# micro.net
KiCad netlist of a schematic drawn in EAGLE
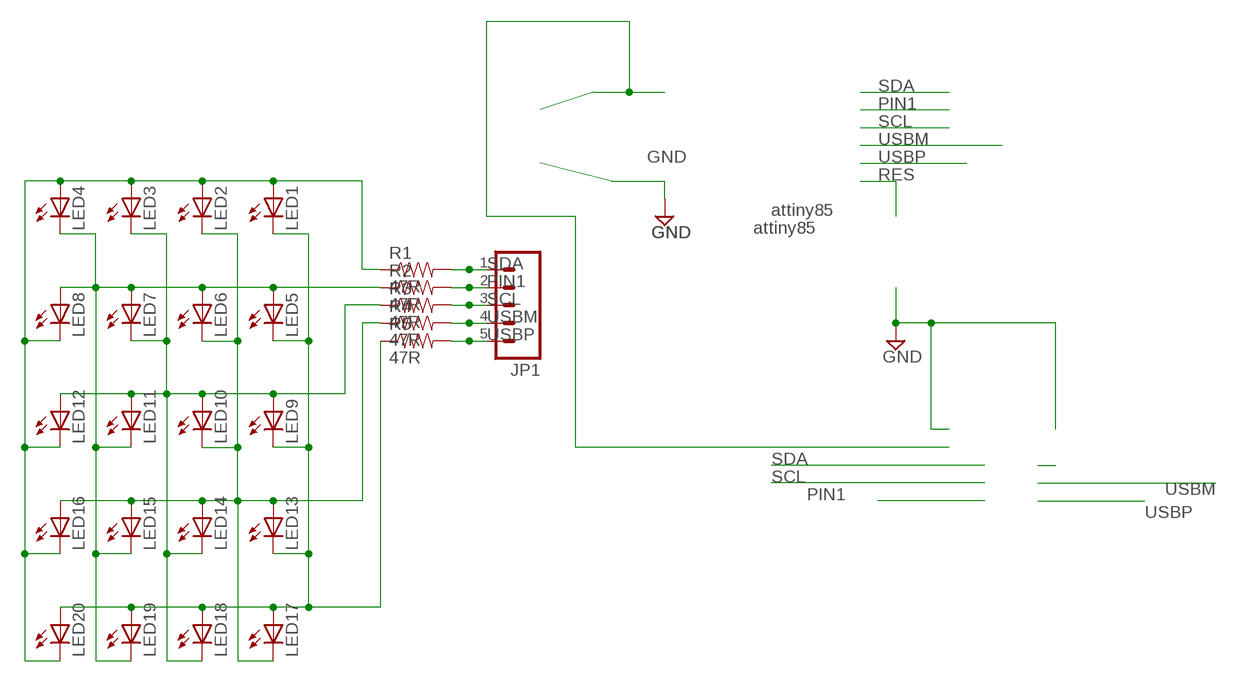
[diagram p0: schematic, sheet 1]

(export (version "E")
  (design (tool "Eeschema 10.0.6"))
  (components
    (comp (ref "JP1")
      (value "M05PTH")
      (footprint "eagle-import:1X05")
      (libsource (lib "eagle-import") (part "M05PTH"))
    )
    (comp (ref "LED1")
      (value "LEDCHIPLED_0603")
      (footprint "eagle-import:CHIPLED_0603")
      (libsource (lib "eagle-import") (part "LEDCHIPLED_0603"))
    )
    (comp (ref "LED2")
      (value "LEDCHIPLED_0603")
      (footprint "eagle-import:CHIPLED_0603")
      (libsource (lib "eagle-import") (part "LEDCHIPLED_0603"))
    )
    (comp (ref "LED3")
      (value "LEDCHIPLED_0603")
      (footprint "eagle-import:CHIPLED_0603")
      (libsource (lib "eagle-import") (part "LEDCHIPLED_0603"))
    )
    (comp (ref "LED4")
      (value "LEDCHIPLED_0603")
      (footprint "eagle-import:CHIPLED_0603")
      (libsource (lib "eagle-import") (part "LEDCHIPLED_0603"))
    )
    (comp (ref "LED5")
      (value "LEDCHIPLED_0603")
      (footprint "eagle-import:CHIPLED_0603")
      (libsource (lib "eagle-import") (part "LEDCHIPLED_0603"))
    )
    (comp (ref "LED6")
      (value "LEDCHIPLED_0603")
      (footprint "eagle-import:CHIPLED_0603")
      (libsource (lib "eagle-import") (part "LEDCHIPLED_0603"))
    )
    (comp (ref "LED7")
      (value "LEDCHIPLED_0603")
      (footprint "eagle-import:CHIPLED_0603")
      (libsource (lib "eagle-import") (part "LEDCHIPLED_0603"))
    )
    (comp (ref "LED8")
      (value "LEDCHIPLED_0603")
      (footprint "eagle-import:CHIPLED_0603")
      (libsource (lib "eagle-import") (part "LEDCHIPLED_0603"))
    )
    (comp (ref "LED9")
      (value "LEDCHIPLED_0603")
      (footprint "eagle-import:CHIPLED_0603")
      (libsource (lib "eagle-import") (part "LEDCHIPLED_0603"))
    )
    (comp (ref "LED10")
      (value "LEDCHIPLED_0603")
      (footprint "eagle-import:CHIPLED_0603")
      (libsource (lib "eagle-import") (part "LEDCHIPLED_0603"))
    )
    (comp (ref "LED11")
      (value "LEDCHIPLED_0603")
      (footprint "eagle-import:CHIPLED_0603")
      (libsource (lib "eagle-import") (part "LEDCHIPLED_0603"))
    )
    (comp (ref "LED12")
      (value "LEDCHIPLED_0603")
      (footprint "eagle-import:CHIPLED_0603")
      (libsource (lib "eagle-import") (part "LEDCHIPLED_0603"))
    )
    (comp (ref "LED13")
      (value "LEDCHIPLED_0603")
      (footprint "eagle-import:CHIPLED_0603")
      (libsource (lib "eagle-import") (part "LEDCHIPLED_0603"))
    )
    (comp (ref "LED14")
      (value "LEDCHIPLED_0603")
      (footprint "eagle-import:CHIPLED_0603")
      (libsource (lib "eagle-import") (part "LEDCHIPLED_0603"))
    )
    (comp (ref "LED15")
      (value "LEDCHIPLED_0603")
      (footprint "eagle-import:CHIPLED_0603")
      (libsource (lib "eagle-import") (part "LEDCHIPLED_0603"))
    )
    (comp (ref "LED16")
      (value "LEDCHIPLED_0603")
      (footprint "eagle-import:CHIPLED_0603")
      (libsource (lib "eagle-import") (part "LEDCHIPLED_0603"))
    )
    (comp (ref "LED17")
      (value "LEDCHIPLED_0603")
      (footprint "eagle-import:CHIPLED_0603")
      (libsource (lib "eagle-import") (part "LEDCHIPLED_0603"))
    )
    (comp (ref "LED18")
      (value "LEDCHIPLED_0603")
      (footprint "eagle-import:CHIPLED_0603")
      (libsource (lib "eagle-import") (part "LEDCHIPLED_0603"))
    )
    (comp (ref "LED19")
      (value "LEDCHIPLED_0603")
      (footprint "eagle-import:CHIPLED_0603")
      (libsource (lib "eagle-import") (part "LEDCHIPLED_0603"))
    )
    (comp (ref "LED20")
      (value "LEDCHIPLED_0603")
      (footprint "eagle-import:CHIPLED_0603")
      (libsource (lib "eagle-import") (part "LEDCHIPLED_0603"))
    )
    (comp (ref "R1")
      (value "47R")
      (footprint "eagle-import:0603-RES")
      (libsource (lib "eagle-import") (part "RESISTOR0603-RES"))
    )
    (comp (ref "R2")
      (value "47R")
      (footprint "eagle-import:0603-RES")
      (libsource (lib "eagle-import") (part "RESISTOR0603-RES"))
    )
    (comp (ref "R3")
      (value "47R")
      (footprint "eagle-import:0603-RES")
      (libsource (lib "eagle-import") (part "RESISTOR0603-RES"))
    )
    (comp (ref "R4")
      (value "47R")
      (footprint "eagle-import:0603-RES")
      (libsource (lib "eagle-import") (part "RESISTOR0603-RES"))
    )
    (comp (ref "R5")
      (value "47R")
      (footprint "eagle-import:0603-RES")
      (libsource (lib "eagle-import") (part "RESISTOR0603-RES"))
    )
  )
  (nets
    (net (code "1") (name "/PIN1") (class "Default")
      (node (ref "JP1") (pin "2") (pinfunction "2_2") (pintype "passive"))
      (node (ref "R2") (pin "2") (pinfunction "2_2") (pintype "passive"))
    )
    (net (code "3") (name "/SCL") (class "Default")
      (node (ref "JP1") (pin "3") (pinfunction "3_3") (pintype "passive"))
      (node (ref "R3") (pin "2") (pinfunction "2_2") (pintype "passive"))
    )
    (net (code "4") (name "/SDA") (class "Default")
      (node (ref "JP1") (pin "1") (pinfunction "1_1") (pintype "passive"))
      (node (ref "R1") (pin "2") (pinfunction "2_2") (pintype "passive"))
    )
    (net (code "5") (name "/USBM") (class "Default")
      (node (ref "JP1") (pin "4") (pinfunction "4_4") (pintype "passive"))
      (node (ref "R4") (pin "2") (pinfunction "2_2") (pintype "passive"))
    )
    (net (code "6") (name "/USBP") (class "Default")
      (node (ref "JP1") (pin "5") (pinfunction "5_5") (pintype "passive"))
      (node (ref "R5") (pin "2") (pinfunction "2_2") (pintype "passive"))
    )
    (net (code "8") (name "Net-(LED1-PadA)") (class "Default")
      (node (ref "LED1") (pin "A") (pinfunction "A_A") (pintype "passive"))
      (node (ref "LED12") (pin "C") (pinfunction "C_C") (pintype "passive"))
      (node (ref "LED16") (pin "C") (pinfunction "C_C") (pintype "passive"))
      (node (ref "LED2") (pin "A") (pinfunction "A_A") (pintype "passive"))
      (node (ref "LED20") (pin "C") (pinfunction "C_C") (pintype "passive"))
      (node (ref "LED3") (pin "A") (pinfunction "A_A") (pintype "passive"))
      (node (ref "LED4") (pin "A") (pinfunction "A_A") (pintype "passive"))
      (node (ref "LED8") (pin "C") (pinfunction "C_C") (pintype "passive"))
      (node (ref "R1") (pin "1") (pinfunction "1_1") (pintype "passive"))
    )
    (net (code "9") (name "Net-(LED1-PadC)") (class "Default")
      (node (ref "LED1") (pin "C") (pinfunction "C_C") (pintype "passive"))
      (node (ref "LED13") (pin "C") (pinfunction "C_C") (pintype "passive"))
      (node (ref "LED17") (pin "A") (pinfunction "A_A") (pintype "passive"))
      (node (ref "LED18") (pin "A") (pinfunction "A_A") (pintype "passive"))
      (node (ref "LED19") (pin "A") (pinfunction "A_A") (pintype "passive"))
      (node (ref "LED20") (pin "A") (pinfunction "A_A") (pintype "passive"))
      (node (ref "LED5") (pin "C") (pinfunction "C_C") (pintype "passive"))
      (node (ref "LED9") (pin "C") (pinfunction "C_C") (pintype "passive"))
      (node (ref "R5") (pin "1") (pinfunction "1_1") (pintype "passive"))
    )
    (net (code "10") (name "Net-(LED10-PadA)") (class "Default")
      (node (ref "LED10") (pin "A") (pinfunction "A_A") (pintype "passive"))
      (node (ref "LED11") (pin "A") (pinfunction "A_A") (pintype "passive"))
      (node (ref "LED12") (pin "A") (pinfunction "A_A") (pintype "passive"))
      (node (ref "LED14") (pin "C") (pinfunction "C_C") (pintype "passive"))
      (node (ref "LED18") (pin "C") (pinfunction "C_C") (pintype "passive"))
      (node (ref "LED3") (pin "C") (pinfunction "C_C") (pintype "passive"))
      (node (ref "LED7") (pin "C") (pinfunction "C_C") (pintype "passive"))
      (node (ref "LED9") (pin "A") (pinfunction "A_A") (pintype "passive"))
      (node (ref "R3") (pin "1") (pinfunction "1_1") (pintype "passive"))
    )
    (net (code "11") (name "Net-(LED10-PadC)") (class "Default")
      (node (ref "LED10") (pin "C") (pinfunction "C_C") (pintype "passive"))
      (node (ref "LED13") (pin "A") (pinfunction "A_A") (pintype "passive"))
      (node (ref "LED14") (pin "A") (pinfunction "A_A") (pintype "passive"))
      (node (ref "LED15") (pin "A") (pinfunction "A_A") (pintype "passive"))
      (node (ref "LED16") (pin "A") (pinfunction "A_A") (pintype "passive"))
      (node (ref "LED17") (pin "C") (pinfunction "C_C") (pintype "passive"))
      (node (ref "LED2") (pin "C") (pinfunction "C_C") (pintype "passive"))
      (node (ref "LED6") (pin "C") (pinfunction "C_C") (pintype "passive"))
      (node (ref "R4") (pin "1") (pinfunction "1_1") (pintype "passive"))
    )
    (net (code "12") (name "Net-(LED11-PadC)") (class "Default")
      (node (ref "LED11") (pin "C") (pinfunction "C_C") (pintype "passive"))
      (node (ref "LED15") (pin "C") (pinfunction "C_C") (pintype "passive"))
      (node (ref "LED19") (pin "C") (pinfunction "C_C") (pintype "passive"))
      (node (ref "LED4") (pin "C") (pinfunction "C_C") (pintype "passive"))
      (node (ref "LED5") (pin "A") (pinfunction "A_A") (pintype "passive"))
      (node (ref "LED6") (pin "A") (pinfunction "A_A") (pintype "passive"))
      (node (ref "LED7") (pin "A") (pinfunction "A_A") (pintype "passive"))
      (node (ref "LED8") (pin "A") (pinfunction "A_A") (pintype "passive"))
      (node (ref "R2") (pin "1") (pinfunction "1_1") (pintype "passive"))
    )
  )
)
